# InputDriver.net
KiCad netlist of a schematic drawn in Altium Designer
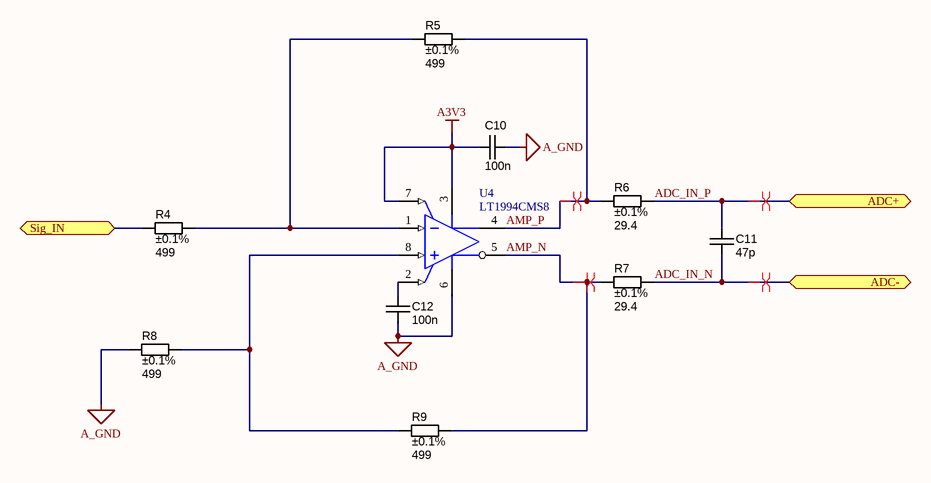
[diagram p0: InputDriver.SchDoc]

(export (version "E")
  (design (tool "Eeschema 10.0.6"))
  (components
    (comp (ref "C10")
      (value "100n")
      (footprint "CAPC2012X135N")
      (description "Capacitor SMD Cer 100nF 10% 16V X5R 0402")
      (fields (field (name "TOLERANCE") "±10%"))
      (libsource (lib "PBL - Capacitors") (part "CAPC_100n_0402_X5R_16V_10%"))
    )
    (comp (ref "C11")
      (value "47p")
      (footprint "CAPC2012X135N")
      (description "Capacitor SMD Cer 39pF 1% 50V NP0 0603")
      (fields (field (name "TOLERANCE") "±1%"))
      (libsource (lib "PBL - Capacitors") (part "CAPC_39p_0603_NP0_50V_1%"))
    )
    (comp (ref "C12")
      (value "100n")
      (footprint "CAPC2012X135N")
      (description "Capacitor SMD Cer 100nF 10% 16V X5R 0402")
      (fields (field (name "TOLERANCE") "±10%"))
      (libsource (lib "PBL - Capacitors") (part "CAPC_100n_0402_X5R_16V_10%"))
    )
    (comp (ref "R4")
      (value "499")
      (footprint "RESC2012X70N")
      (description "Resistor SMD chip 1k Ohm 0.125W 1% 0805")
      (fields (field (name "TOLERANCE") "±0.1%") (field (name "Comment") "Thick Film"))
      (libsource (lib "PBL - Resistors") (part "RES_1K_0805_1%"))
    )
    (comp (ref "R5")
      (value "499")
      (footprint "RESC2012X70N")
      (description "Resistor SMD chip 1k Ohm 0.125W 1% 0805")
      (fields (field (name "TOLERANCE") "±0.1%") (field (name "Comment") "Thick Film"))
      (libsource (lib "PBL - Resistors") (part "RES_1K_0805_1%"))
    )
    (comp (ref "R6")
      (value "29.4")
      (footprint "RESC2012X70N")
      (description "Resistor SMD chip 1k Ohm 0.125W 1% 0805")
      (fields (field (name "TOLERANCE") "±0.1%") (field (name "Comment") "Thick Film"))
      (libsource (lib "PBL - Resistors") (part "RES_1K_0805_1%"))
    )
    (comp (ref "R7")
      (value "29.4")
      (footprint "RESC2012X70N")
      (description "Resistor SMD chip 1k Ohm 0.125W 1% 0805")
      (fields (field (name "TOLERANCE") "±0.1%") (field (name "Comment") "Thick Film"))
      (libsource (lib "PBL - Resistors") (part "RES_1K_0805_1%"))
    )
    (comp (ref "R8")
      (value "499")
      (footprint "RESC2012X70N")
      (description "Resistor SMD chip 1k Ohm 0.125W 1% 0805")
      (fields (field (name "TOLERANCE") "±0.1%") (field (name "Comment") "Thick Film"))
      (libsource (lib "PBL - Resistors") (part "RES_1K_0805_1%"))
    )
    (comp (ref "R9")
      (value "499")
      (footprint "RESC2012X70N")
      (description "Resistor SMD chip 1k Ohm 0.125W 1% 0805")
      (fields (field (name "TOLERANCE") "±0.1%") (field (name "Comment") "Thick Film"))
      (libsource (lib "PBL - Resistors") (part "RES_1K_0805_1%"))
    )
    (comp (ref "U4")
      (value "LT1994CMS8")
      (footprint "LT-MS8-8_N")
      (fields
        (field (name "LINEAR TECHNOLOGY PART NUMBER") "LT1994")
        (field (name "MANUFACTURER") "Linear Technology")
      )
      (libsource (lib "Linear Technology Operational Amplifiers (LT1000)") (part "LT1994CMS8"))
    )
  )
  (nets
    (net (code "1") (name "/ADC_IN_N") (class "Default")
      (node (ref "C11") (pin "2") (pintype "passive"))
      (node (ref "R7") (pin "2") (pinfunction "2_2") (pintype "passive"))
    )
    (net (code "2") (name "/ADC_IN_P") (class "Default")
      (node (ref "C11") (pin "1") (pintype "passive"))
      (node (ref "R6") (pin "2") (pinfunction "2_2") (pintype "passive"))
    )
    (net (code "3") (name "/AMP_N") (class "Default")
      (node (ref "R7") (pin "1") (pinfunction "1_1") (pintype "passive"))
      (node (ref "R9") (pin "2") (pinfunction "2_2") (pintype "passive"))
      (node (ref "U4") (pin "5") (pinfunction "OUT-_5") (pintype "open_collector"))
    )
    (net (code "4") (name "/AMP_P") (class "Default")
      (node (ref "R5") (pin "2") (pinfunction "2_2") (pintype "passive"))
      (node (ref "R6") (pin "1") (pinfunction "1_1") (pintype "passive"))
      (node (ref "U4") (pin "4") (pinfunction "OUT+_4") (pintype "open_collector"))
    )
    (net (code "5") (name "/Sig_IN") (class "Default")
      (node (ref "R4") (pin "1") (pinfunction "1_1") (pintype "passive"))
    )
    (net (code "6") (name "A3V3") (class "Default")
      (node (ref "C10") (pin "1") (pintype "passive"))
      (node (ref "U4") (pin "3") (pinfunction "V+_3") (pintype "power_in"))
      (node (ref "U4") (pin "7") (pinfunction "~{SHDN}_7") (pintype "input"))
    )
    (net (code "7") (name "A_GND") (class "Default")
      (node (ref "C10") (pin "2") (pintype "passive"))
      (node (ref "C12") (pin "2") (pintype "passive"))
      (node (ref "R8") (pin "1") (pinfunction "1_1") (pintype "passive"))
      (node (ref "U4") (pin "6") (pinfunction "V-_6") (pintype "power_in"))
    )
    (net (code "8") (name "Net-(U4-IN+)") (class "Default")
      (node (ref "R8") (pin "2") (pinfunction "2_2") (pintype "passive"))
      (node (ref "R9") (pin "1") (pinfunction "1_1") (pintype "passive"))
      (node (ref "U4") (pin "8") (pinfunction "IN+_8") (pintype "input"))
    )
    (net (code "9") (name "Net-(U4-IN-)") (class "Default")
      (node (ref "R4") (pin "2") (pinfunction "2_2") (pintype "passive"))
      (node (ref "R5") (pin "1") (pinfunction "1_1") (pintype "passive"))
      (node (ref "U4") (pin "1") (pinfunction "IN-_1") (pintype "input"))
    )
    (net (code "10") (name "Net-(U4-VOCM)") (class "Default")
      (node (ref "C12") (pin "1") (pintype "passive"))
      (node (ref "U4") (pin "2") (pinfunction "VOCM_2") (pintype "input"))
    )
  )
)
